# CAN_Interface.net
KiCad netlist of a schematic drawn in Altium Designer
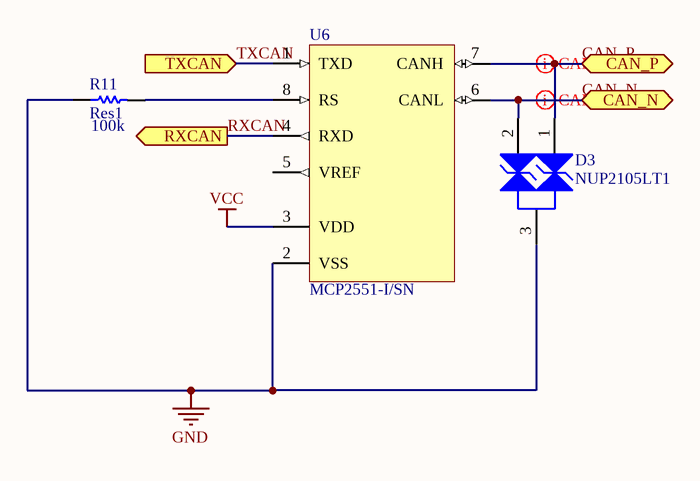
[diagram p0: CAN_Interface.SchDoc]

(export (version "E")
  (design (tool "Eeschema 10.0.6"))
  (components
    (comp (ref "D3")
      (value "NUP2105LT1")
      (footprint "ONSC-SOT-23-3-318-08_V")
      (description "Dual Line CAN Bus Protector, 3-Pin SOT-23, Tape and Reel")
      (fields (field (name "MANUFACTURER") "On Semiconductor"))
      (libsource (lib "Altium Content Vault") (part "ONSC-NUP21X5X-SOT-23-3-318-08"))
    )
    (comp (ref "R11")
      (value "Res1")
      (footprint "6-0805_L")
      (description "Resistor")
      (fields (field (name "ALTIUM_VALUE") "100k") (field (name "PUBLISHER") "Altium Limited"))
      (libsource (lib "Miscellaneous Devices") (part "Res1"))
    )
    (comp (ref "U6")
      (value "MCP2551-I/SN")
      (footprint "SOIC-SN8_N")
      (description "High-Speed CAN Transceiver, 8-Pin SOIC, Industrial Temperature")
      (libsource (lib "Altium Content Vault") (part "COM-TRX-MCP2551-8"))
    )
  )
  (nets
    (net (code "1") (name "/CAN_N") (class "Default")
      (node (ref "D3") (pin "2") (pinfunction "K_2") (pintype "passive"))
      (node (ref "U6") (pin "6") (pinfunction "CANL_6") (pintype "bidirectional"))
    )
    (net (code "2") (name "/CAN_P") (class "Default")
      (node (ref "D3") (pin "1") (pinfunction "K_1") (pintype "passive"))
      (node (ref "U6") (pin "7") (pinfunction "CANH_7") (pintype "bidirectional"))
    )
    (net (code "3") (name "/RXCAN") (class "Default")
      (node (ref "U6") (pin "4") (pinfunction "RXD_4") (pintype "output"))
    )
    (net (code "4") (name "/TXCAN") (class "Default")
      (node (ref "U6") (pin "1") (pinfunction "TXD_1") (pintype "input"))
    )
    (net (code "5") (name "GND") (class "Default")
      (node (ref "D3") (pin "3") (pinfunction "K_3") (pintype "passive"))
      (node (ref "R11") (pin "1") (pinfunction "1_1") (pintype "passive"))
      (node (ref "U6") (pin "2") (pinfunction "VSS_2") (pintype "power_in"))
    )
    (net (code "6") (name "Net-(U6-RS)") (class "Default")
      (node (ref "R11") (pin "2") (pinfunction "2_2") (pintype "passive"))
      (node (ref "U6") (pin "8") (pinfunction "RS_8") (pintype "input"))
    )
    (net (code "7") (name "VCC") (class "Default")
      (node (ref "U6") (pin "3") (pinfunction "VDD_3") (pintype "power_in"))
    )
    (net (code "8") (name "unconnected-(U6-VREF-Pad5)") (class "Default")
      (node (ref "U6") (pin "5") (pinfunction "VREF_5") (pintype "output"))
    )
  )
)
